# Moteino_RTC_Shield_v2.net
KiCad netlist of a schematic drawn in EAGLE
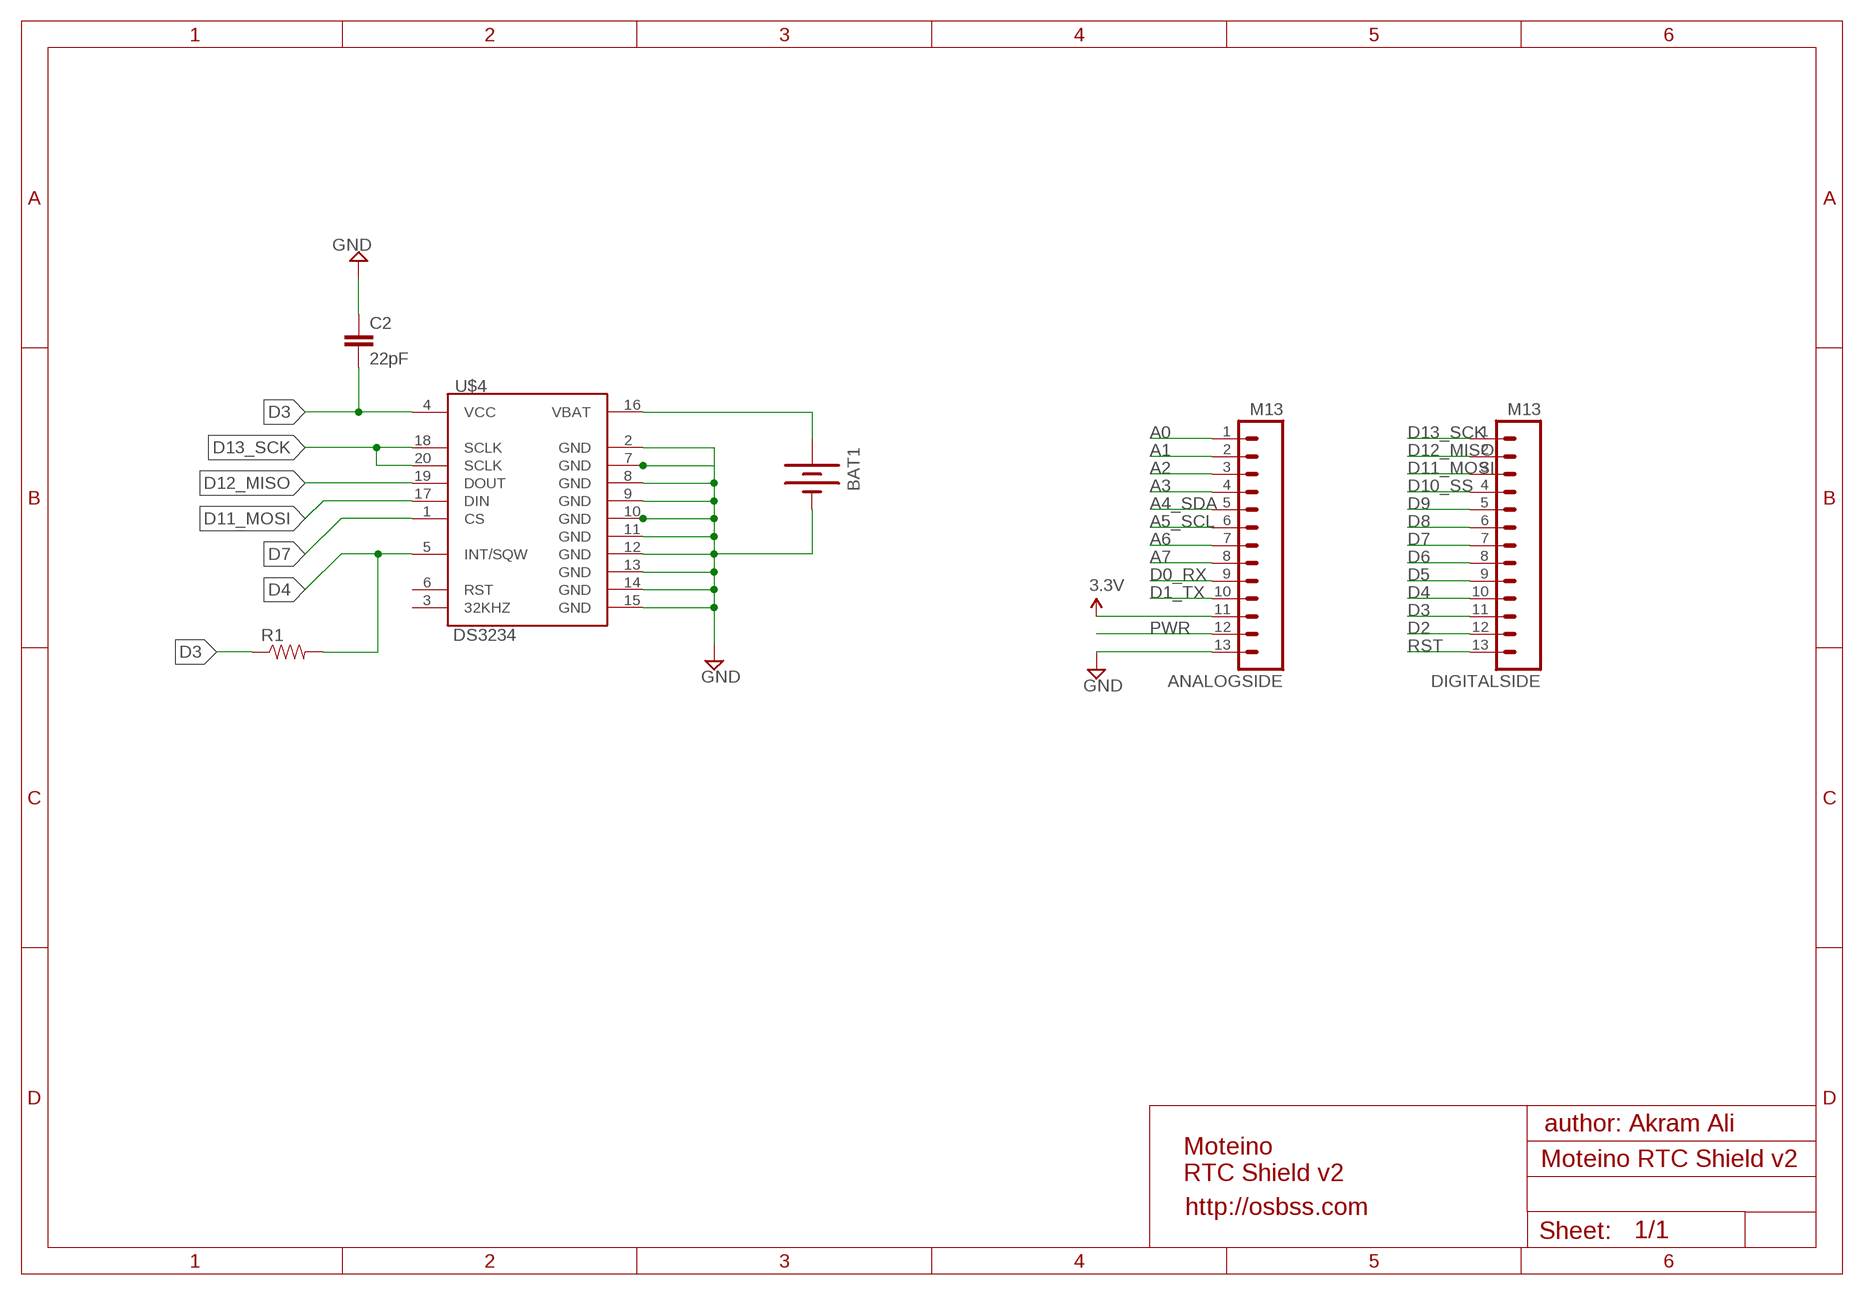
[diagram p0: schematic, sheet 1]

(export (version "E")
  (design (tool "Eeschema 10.0.6"))
  (components
    (comp (ref "ANALOGSIDE")
      (value "M13")
      (footprint "eagle-import:1X13")
      (libsource (lib "eagle-import") (part "M13"))
    )
    (comp (ref "BAT1")
      (value "BATTERY12MM")
      (footprint "eagle-import:BATTCON_12MM")
      (libsource (lib "eagle-import") (part "BATTERY12MM"))
    )
    (comp (ref "C2")
      (value "22pF")
      (footprint "eagle-import:0805")
      (libsource (lib "eagle-import") (part "CAP0805"))
    )
    (comp (ref "DIGITALSIDE")
      (value "M13")
      (footprint "eagle-import:1X13")
      (libsource (lib "eagle-import") (part "M13"))
    )
    (comp (ref "R1")
      (value "RESISTOR0805-RES")
      (footprint "eagle-import:0805")
      (libsource (lib "eagle-import") (part "RESISTOR0805-RES"))
    )
    (comp (ref "U$4")
      (value "DS3234")
      (footprint "eagle-import:DS3234")
      (libsource (lib "eagle-import") (part "DS3234"))
    )
  )
  (nets
    (net (code "1") (name "/A0") (class "Default")
      (node (ref "ANALOGSIDE") (pin "1") (pinfunction "1_1") (pintype "passive"))
    )
    (net (code "2") (name "/A1") (class "Default")
      (node (ref "ANALOGSIDE") (pin "2") (pinfunction "2_2") (pintype "passive"))
    )
    (net (code "3") (name "/A2") (class "Default")
      (node (ref "ANALOGSIDE") (pin "3") (pinfunction "3_3") (pintype "passive"))
    )
    (net (code "4") (name "/A3") (class "Default")
      (node (ref "ANALOGSIDE") (pin "4") (pinfunction "4_4") (pintype "passive"))
    )
    (net (code "5") (name "/A4_SDA") (class "Default")
      (node (ref "ANALOGSIDE") (pin "5") (pinfunction "5_5") (pintype "passive"))
    )
    (net (code "6") (name "/A5_SCL") (class "Default")
      (node (ref "ANALOGSIDE") (pin "6") (pinfunction "6_6") (pintype "passive"))
    )
    (net (code "7") (name "/A6") (class "Default")
      (node (ref "ANALOGSIDE") (pin "7") (pinfunction "7_7") (pintype "passive"))
    )
    (net (code "8") (name "/A7") (class "Default")
      (node (ref "ANALOGSIDE") (pin "8") (pinfunction "8_8") (pintype "passive"))
    )
    (net (code "9") (name "/D0_RX") (class "Default")
      (node (ref "ANALOGSIDE") (pin "9") (pinfunction "9_9") (pintype "passive"))
    )
    (net (code "10") (name "/D1_TX") (class "Default")
      (node (ref "ANALOGSIDE") (pin "10") (pinfunction "10_10") (pintype "passive"))
    )
    (net (code "11") (name "/D2") (class "Default")
      (node (ref "DIGITALSIDE") (pin "12") (pinfunction "12_12") (pintype "passive"))
    )
    (net (code "12") (name "/D5") (class "Default")
      (node (ref "DIGITALSIDE") (pin "9") (pinfunction "9_9") (pintype "passive"))
    )
    (net (code "13") (name "/D6") (class "Default")
      (node (ref "DIGITALSIDE") (pin "8") (pinfunction "8_8") (pintype "passive"))
    )
    (net (code "14") (name "/D8") (class "Default")
      (node (ref "DIGITALSIDE") (pin "6") (pinfunction "6_6") (pintype "passive"))
    )
    (net (code "15") (name "/D9") (class "Default")
      (node (ref "DIGITALSIDE") (pin "5") (pinfunction "5_5") (pintype "passive"))
    )
    (net (code "16") (name "/D10_SS") (class "Default")
      (node (ref "DIGITALSIDE") (pin "4") (pinfunction "4_4") (pintype "passive"))
    )
    (net (code "17") (name "/PWR") (class "Default")
      (node (ref "ANALOGSIDE") (pin "12") (pinfunction "12_12") (pintype "passive"))
    )
    (net (code "18") (name "/RST") (class "Default")
      (node (ref "DIGITALSIDE") (pin "13") (pinfunction "13_13") (pintype "passive"))
    )
    (net (code "19") (name "3.3V") (class "Default")
      (node (ref "ANALOGSIDE") (pin "11") (pinfunction "11_11") (pintype "passive"))
    )
    (net (code "20") (name "D3") (class "Default")
      (node (ref "C2") (pin "2") (pinfunction "2_2") (pintype "passive"))
      (node (ref "DIGITALSIDE") (pin "11") (pinfunction "11_11") (pintype "passive"))
      (node (ref "R1") (pin "1") (pinfunction "1_1") (pintype "passive"))
      (node (ref "U$4") (pin "4") (pinfunction "VCC_4") (pintype "bidirectional"))
    )
    (net (code "21") (name "D4") (class "Default")
      (node (ref "DIGITALSIDE") (pin "10") (pinfunction "10_10") (pintype "passive"))
      (node (ref "R1") (pin "2") (pinfunction "2_2") (pintype "passive"))
      (node (ref "U$4") (pin "5") (pinfunction "INT/SQW_5") (pintype "bidirectional"))
    )
    (net (code "22") (name "D7") (class "Default")
      (node (ref "DIGITALSIDE") (pin "7") (pinfunction "7_7") (pintype "passive"))
      (node (ref "U$4") (pin "1") (pinfunction "CS_1") (pintype "bidirectional"))
    )
    (net (code "23") (name "D11_MOSI") (class "Default")
      (node (ref "DIGITALSIDE") (pin "3") (pinfunction "3_3") (pintype "passive"))
      (node (ref "U$4") (pin "17") (pinfunction "DIN_17") (pintype "bidirectional"))
    )
    (net (code "24") (name "D12_MISO") (class "Default")
      (node (ref "DIGITALSIDE") (pin "2") (pinfunction "2_2") (pintype "passive"))
      (node (ref "U$4") (pin "19") (pinfunction "DOUT_19") (pintype "bidirectional"))
    )
    (net (code "25") (name "D13_SCK") (class "Default")
      (node (ref "DIGITALSIDE") (pin "1") (pinfunction "1_1") (pintype "passive"))
      (node (ref "U$4") (pin "18") (pinfunction "SCLK_18") (pintype "bidirectional"))
      (node (ref "U$4") (pin "20") (pinfunction "SCLK_20") (pintype "bidirectional"))
    )
    (net (code "26") (name "GND") (class "Default")
      (node (ref "ANALOGSIDE") (pin "13") (pinfunction "13_13") (pintype "passive"))
      (node (ref "BAT1") (pin "GND") (pinfunction "-_GND") (pintype "power_in"))
      (node (ref "C2") (pin "1") (pinfunction "1_1") (pintype "passive"))
      (node (ref "U$4") (pin "10") (pinfunction "GND_10") (pintype "bidirectional"))
      (node (ref "U$4") (pin "11") (pinfunction "GND_11") (pintype "bidirectional"))
      (node (ref "U$4") (pin "12") (pinfunction "GND_12") (pintype "bidirectional"))
      (node (ref "U$4") (pin "13") (pinfunction "GND_13") (pintype "bidirectional"))
      (node (ref "U$4") (pin "14") (pinfunction "GND_14") (pintype "bidirectional"))
      (node (ref "U$4") (pin "15") (pinfunction "GND_15") (pintype "bidirectional"))
      (node (ref "U$4") (pin "2") (pinfunction "GND_2") (pintype "bidirectional"))
      (node (ref "U$4") (pin "7") (pinfunction "GND_7") (pintype "bidirectional"))
      (node (ref "U$4") (pin "8") (pinfunction "GND_8") (pintype "bidirectional"))
      (node (ref "U$4") (pin "9") (pinfunction "GND_9") (pintype "bidirectional"))
    )
    (net (code "27") (name "Net-(BAT1-+)") (class "Default")
      (node (ref "BAT1") (pin "PWR@1") (pinfunction "+_PWR@1") (pintype "power_in"))
      (node (ref "U$4") (pin "16") (pinfunction "VBAT_16") (pintype "bidirectional"))
    )
    (net (code "28") (name "unconnected-(U$4-32KHZ-Pad3)") (class "Default")
      (node (ref "U$4") (pin "3") (pinfunction "32KHZ_3") (pintype "bidirectional"))
    )
    (net (code "29") (name "unconnected-(U$4-RST-Pad6)") (class "Default")
      (node (ref "U$4") (pin "6") (pinfunction "RST_6") (pintype "bidirectional"))
    )
  )
)
